# Ethernet.net
KiCad netlist of a schematic drawn in Altium Designer
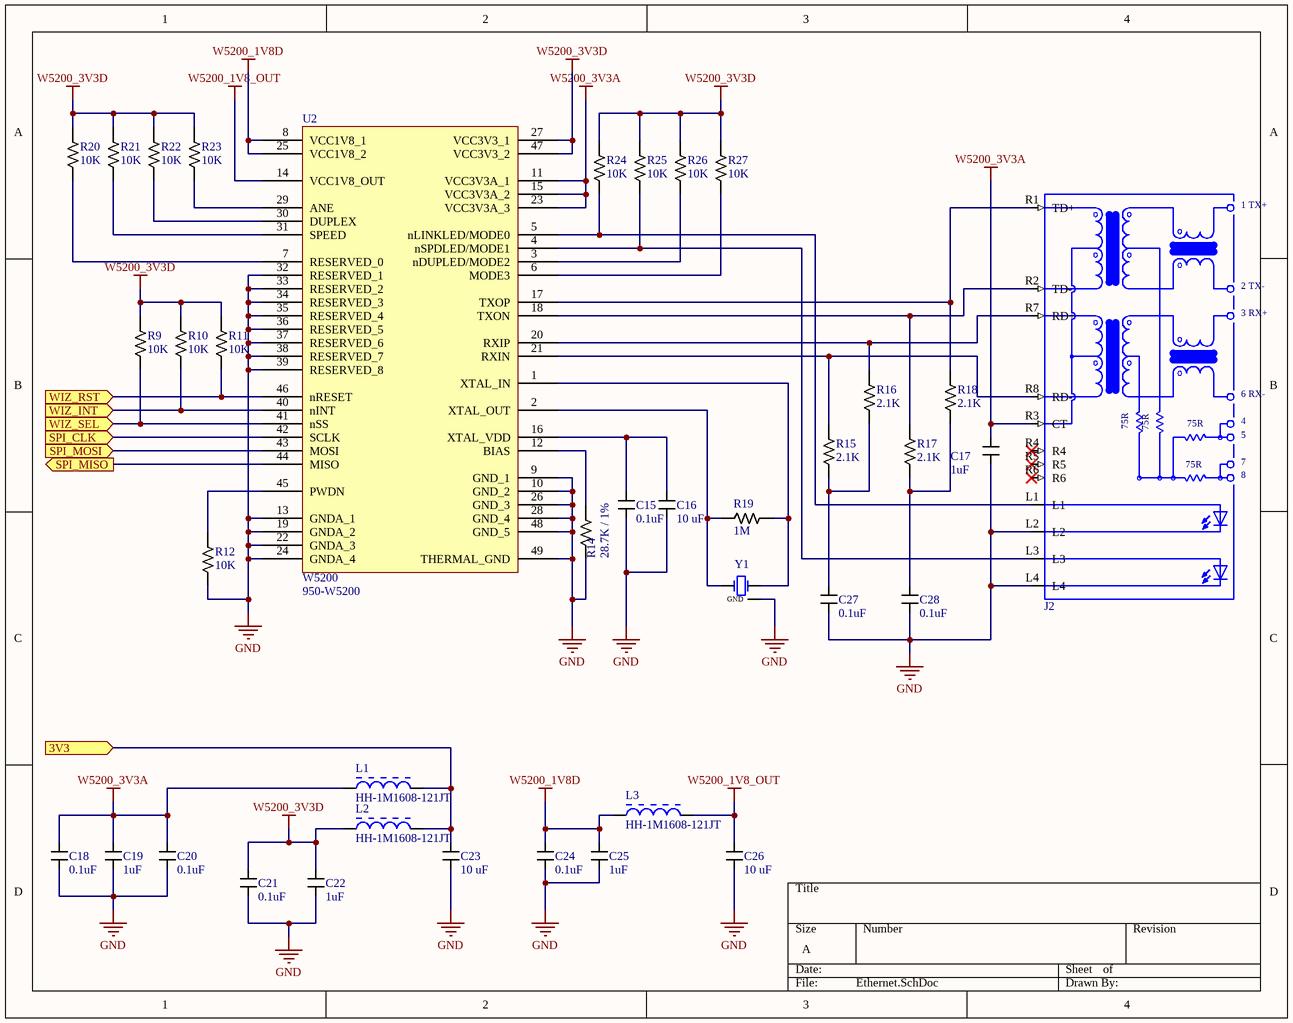
[diagram p0: Ethernet.SchDoc]

(export (version "E")
  (design (tool "Eeschema 10.0.6"))
  (components
    (comp (ref "C15")
      (value "0.1uF")
      (footprint "CAPACITOR_0603")
      (description "Cap 100nF 6.3V +/-10%\r\nCeramic 0603")
      (fields
        (field (name "TOLERANCE") "+/- 10%")
        (field (name "VOLTAGE") "6.3V")
        (field (name "MADE BY") "Flip B")
      )
      (libsource (lib "Capacitors") (part "CAPACITOR_0.1uF_0603"))
    )
    (comp (ref "C16")
      (value "10uF Ceramic 6.3V")
      (footprint "CAPACITOR_0603")
      (description "Cap 10uF 6.3V +/-20%\r\nCeramic 0603")
      (fields
        (field (name "TOLERANCE") "+/- 20%")
        (field (name "VOLTAGE") "6.3V")
        (field (name "VALUE (UF)") "10 uF")
        (field (name "MADE BY") "Flip B")
      )
      (libsource (lib "Capacitors") (part "CAPACITOR_10uF_0603"))
    )
    (comp (ref "C17")
      (value "1uF")
      (footprint "CAPACITOR_0603")
      (description "Cap 1uF 16V +/-10%\r\nCeramic 0603")
      (fields
        (field (name "TOLERANCE") "+/- 10%")
        (field (name "VOLTAGE") "16V")
        (field (name "MADE BY") "Flip B")
      )
      (libsource (lib "Capacitors") (part "CAPACITOR_1uF_0603"))
    )
    (comp (ref "C18")
      (value "0.1uF")
      (footprint "CAPACITOR_0603")
      (description "Cap 100nF 6.3V +/-10%\r\nCeramic 0603")
      (fields
        (field (name "TOLERANCE") "+/- 10%")
        (field (name "VOLTAGE") "6.3V")
        (field (name "MADE BY") "Flip B")
      )
      (libsource (lib "Capacitors") (part "CAPACITOR_0.1uF_0603"))
    )
    (comp (ref "C19")
      (value "1uF")
      (footprint "CAPACITOR_0603")
      (description "Cap 1uF 16V +/-10%\r\nCeramic 0603")
      (fields
        (field (name "TOLERANCE") "+/- 10%")
        (field (name "VOLTAGE") "16V")
        (field (name "MADE BY") "Flip B")
      )
      (libsource (lib "Capacitors") (part "CAPACITOR_1uF_0603"))
    )
    (comp (ref "C20")
      (value "0.1uF")
      (footprint "CAPACITOR_0603")
      (description "Cap 100nF 6.3V +/-10%\r\nCeramic 0603")
      (fields
        (field (name "TOLERANCE") "+/- 10%")
        (field (name "VOLTAGE") "6.3V")
        (field (name "MADE BY") "Flip B")
      )
      (libsource (lib "Capacitors") (part "CAPACITOR_0.1uF_0603"))
    )
    (comp (ref "C21")
      (value "0.1uF")
      (footprint "CAPACITOR_0603")
      (description "Cap 100nF 6.3V +/-10%\r\nCeramic 0603")
      (fields
        (field (name "TOLERANCE") "+/- 10%")
        (field (name "VOLTAGE") "6.3V")
        (field (name "MADE BY") "Flip B")
      )
      (libsource (lib "Capacitors") (part "CAPACITOR_0.1uF_0603"))
    )
    (comp (ref "C22")
      (value "1uF")
      (footprint "CAPACITOR_0603")
      (description "Cap 1uF 16V +/-10%\r\nCeramic 0603")
      (fields
        (field (name "TOLERANCE") "+/- 10%")
        (field (name "VOLTAGE") "16V")
        (field (name "MADE BY") "Flip B")
      )
      (libsource (lib "Capacitors") (part "CAPACITOR_1uF_0603"))
    )
    (comp (ref "C23")
      (value "10uF Ceramic 6.3V")
      (footprint "CAPACITOR_0603")
      (description "Cap 10uF 6.3V +/-20%\r\nCeramic 0603")
      (fields
        (field (name "TOLERANCE") "+/- 20%")
        (field (name "VOLTAGE") "6.3V")
        (field (name "VALUE (UF)") "10 uF")
        (field (name "MADE BY") "Flip B")
      )
      (libsource (lib "Capacitors") (part "CAPACITOR_10uF_0603"))
    )
    (comp (ref "C24")
      (value "0.1uF")
      (footprint "CAPACITOR_0603")
      (description "Cap 100nF 6.3V +/-10%\r\nCeramic 0603")
      (fields
        (field (name "TOLERANCE") "+/- 10%")
        (field (name "VOLTAGE") "6.3V")
        (field (name "MADE BY") "Flip B")
      )
      (libsource (lib "Capacitors") (part "CAPACITOR_0.1uF_0603"))
    )
    (comp (ref "C25")
      (value "1uF")
      (footprint "CAPACITOR_0603")
      (description "Cap 1uF 16V +/-10%\r\nCeramic 0603")
      (fields
        (field (name "TOLERANCE") "+/- 10%")
        (field (name "VOLTAGE") "16V")
        (field (name "MADE BY") "Flip B")
      )
      (libsource (lib "Capacitors") (part "CAPACITOR_1uF_0603"))
    )
    (comp (ref "C26")
      (value "10uF Ceramic 6.3V")
      (footprint "CAPACITOR_0603")
      (description "Cap 10uF 6.3V +/-20%\r\nCeramic 0603")
      (fields
        (field (name "TOLERANCE") "+/- 20%")
        (field (name "VOLTAGE") "6.3V")
        (field (name "VALUE (UF)") "10 uF")
        (field (name "MADE BY") "Flip B")
      )
      (libsource (lib "Capacitors") (part "CAPACITOR_10uF_0603"))
    )
    (comp (ref "C27")
      (value "0.1uF")
      (footprint "CAPACITOR_0603")
      (description "Cap 100nF 6.3V +/-10%\r\nCeramic 0603")
      (fields
        (field (name "TOLERANCE") "+/- 10%")
        (field (name "VOLTAGE") "6.3V")
        (field (name "MADE BY") "Flip B")
      )
      (libsource (lib "Capacitors") (part "CAPACITOR_0.1uF_0603"))
    )
    (comp (ref "C28")
      (value "0.1uF")
      (footprint "CAPACITOR_0603")
      (description "Cap 100nF 6.3V +/-10%\r\nCeramic 0603")
      (fields
        (field (name "TOLERANCE") "+/- 10%")
        (field (name "VOLTAGE") "6.3V")
        (field (name "MADE BY") "Flip B")
      )
      (libsource (lib "Capacitors") (part "CAPACITOR_0.1uF_0603"))
    )
    (comp (ref "J2")
      (value "Ethernet Connector")
      (footprint "WIZNET_RB1-125BAG1A")
      (description "CONN JACK 1PORT 100 BASE-T PCB")
      (libsource (lib "Connectors") (part "RB1-125BAG1A"))
    )
    (comp (ref "L1")
      (value "HH-1M1608-121JT")
      (footprint "CTC-1608_L")
      (description "Chip Ferrite Bead, 0.14 Ohm, 1.1 A, -55 to 125 degC, 2-Pin SMD, RoHS, Tape and Reel")
      (fields (field (name "MANUFACTURER") "CTC Coils") (field (name "PARTNUMBER") "HH-1M1608"))
      (libsource (lib "Altium Content Vault") (part "IND-FB-2"))
    )
    (comp (ref "L2")
      (value "HH-1M1608-121JT")
      (footprint "CTC-1608_L")
      (description "Chip Ferrite Bead, 0.14 Ohm, 1.1 A, -55 to 125 degC, 2-Pin SMD, RoHS, Tape and Reel")
      (fields (field (name "MANUFACTURER") "CTC Coils") (field (name "PARTNUMBER") "HH-1M1608"))
      (libsource (lib "Altium Content Vault") (part "IND-FB-2"))
    )
    (comp (ref "L3")
      (value "HH-1M1608-121JT")
      (footprint "CTC-1608_L")
      (description "Chip Ferrite Bead, 0.14 Ohm, 1.1 A, -55 to 125 degC, 2-Pin SMD, RoHS, Tape and Reel")
      (fields (field (name "MANUFACTURER") "CTC Coils") (field (name "PARTNUMBER") "HH-1M1608"))
      (libsource (lib "Altium Content Vault") (part "IND-FB-2"))
    )
    (comp (ref "R9")
      (value "10k Ohm 5% 1/10W")
      (footprint "RESISTOR_0603")
      (description "RES 10k OHM 5% 1/10W 0603")
      (fields
        (field (name "TOLERANCE") "+/- 5%")
        (field (name "VALUE  (OHMS)") "10K")
        (field (name "MADE BY") "Robert Pafford")
      )
      (libsource (lib "Resistors") (part "RESISTOR_10K_0603"))
    )
    (comp (ref "R10")
      (value "10k Ohm 5% 1/10W")
      (footprint "RESISTOR_0603")
      (description "RES 10k OHM 5% 1/10W 0603")
      (fields
        (field (name "TOLERANCE") "+/- 5%")
        (field (name "VALUE  (OHMS)") "10K")
        (field (name "MADE BY") "Robert Pafford")
      )
      (libsource (lib "Resistors") (part "RESISTOR_10K_0603"))
    )
    (comp (ref "R11")
      (value "10k Ohm 5% 1/10W")
      (footprint "RESISTOR_0603")
      (description "RES 10k OHM 5% 1/10W 0603")
      (fields
        (field (name "TOLERANCE") "+/- 5%")
        (field (name "VALUE  (OHMS)") "10K")
        (field (name "MADE BY") "Robert Pafford")
      )
      (libsource (lib "Resistors") (part "RESISTOR_10K_0603"))
    )
    (comp (ref "R12")
      (value "10k Ohm 5% 1/10W")
      (footprint "RESISTOR_0603")
      (description "RES 10k OHM 5% 1/10W 0603")
      (fields
        (field (name "TOLERANCE") "+/- 5%")
        (field (name "VALUE  (OHMS)") "10K")
        (field (name "MADE BY") "Robert Pafford")
      )
      (libsource (lib "Resistors") (part "RESISTOR_10K_0603"))
    )
    (comp (ref "R14")
      (value "K / 1%")
      (footprint "RESISTOR_0603")
      (description "RES 28.7K OHM 1% 1/8W 0603")
      (fields
        (field (name "TOLERANCE") "+/- 5%")
        (field (name "VALUE  (OHMS)") "28.7K / 1%")
        (field (name "MADE BY") "Robert Pafford")
      )
      (libsource (lib "Resistors") (part "RESISTOR_28.7K / 1%_0603_1"))
    )
    (comp (ref "R15")
      (value "2.1k Ohm 5% 1/8W")
      (footprint "RESISTOR_0603")
      (description "RES 2.1k OHM 5% 1/8W 0603")
      (fields
        (field (name "TOLERANCE") "+/- 5%")
        (field (name "VALUE  (OHMS)") "2.1K")
        (field (name "MADE BY") "Robert Pafford")
      )
      (libsource (lib "Resistors") (part "RESISTOR_2.1K_0603_1"))
    )
    (comp (ref "R16")
      (value "2.1k Ohm 5% 1/8W")
      (footprint "RESISTOR_0603")
      (description "RES 2.1k OHM 5% 1/8W 0603")
      (fields
        (field (name "TOLERANCE") "+/- 5%")
        (field (name "VALUE  (OHMS)") "2.1K")
        (field (name "MADE BY") "Robert Pafford")
      )
      (libsource (lib "Resistors") (part "RESISTOR_2.1K_0603_1"))
    )
    (comp (ref "R17")
      (value "2.1k Ohm 5% 1/8W")
      (footprint "RESISTOR_0603")
      (description "RES 2.1k OHM 5% 1/8W 0603")
      (fields
        (field (name "TOLERANCE") "+/- 5%")
        (field (name "VALUE  (OHMS)") "2.1K")
        (field (name "MADE BY") "Robert Pafford")
      )
      (libsource (lib "Resistors") (part "RESISTOR_2.1K_0603_1"))
    )
    (comp (ref "R18")
      (value "2.1k Ohm 5% 1/8W")
      (footprint "RESISTOR_0603")
      (description "RES 2.1k OHM 5% 1/8W 0603")
      (fields
        (field (name "TOLERANCE") "+/- 5%")
        (field (name "VALUE  (OHMS)") "2.1K")
        (field (name "MADE BY") "Robert Pafford")
      )
      (libsource (lib "Resistors") (part "RESISTOR_2.1K_0603_1"))
    )
    (comp (ref "R19")
      (value "1M")
      (footprint "RESISTOR_0603")
      (description "RES 1M OHM 1/8W 0603")
      (fields
        (field (name "TOLERANCE") "+/- 5%")
        (field (name "VALUE  (OHMS)") "1M")
        (field (name "MADE BY") "Robert Pafford")
      )
      (libsource (lib "Resistors") (part "RESISTOR_1M_0603_1"))
    )
    (comp (ref "R20")
      (value "10k Ohm 5% 1/10W")
      (footprint "RESISTOR_0603")
      (description "RES 10k OHM 5% 1/10W 0603")
      (fields
        (field (name "TOLERANCE") "+/- 5%")
        (field (name "VALUE  (OHMS)") "10K")
        (field (name "MADE BY") "Robert Pafford")
      )
      (libsource (lib "Resistors") (part "RESISTOR_10K_0603"))
    )
    (comp (ref "R21")
      (value "10k Ohm 5% 1/10W")
      (footprint "RESISTOR_0603")
      (description "RES 10k OHM 5% 1/10W 0603")
      (fields
        (field (name "TOLERANCE") "+/- 5%")
        (field (name "VALUE  (OHMS)") "10K")
        (field (name "MADE BY") "Robert Pafford")
      )
      (libsource (lib "Resistors") (part "RESISTOR_10K_0603"))
    )
    (comp (ref "R22")
      (value "10k Ohm 5% 1/10W")
      (footprint "RESISTOR_0603")
      (description "RES 10k OHM 5% 1/10W 0603")
      (fields
        (field (name "TOLERANCE") "+/- 5%")
        (field (name "VALUE  (OHMS)") "10K")
        (field (name "MADE BY") "Robert Pafford")
      )
      (libsource (lib "Resistors") (part "RESISTOR_10K_0603"))
    )
    (comp (ref "R23")
      (value "10k Ohm 5% 1/10W")
      (footprint "RESISTOR_0603")
      (description "RES 10k OHM 5% 1/10W 0603")
      (fields
        (field (name "TOLERANCE") "+/- 5%")
        (field (name "VALUE  (OHMS)") "10K")
        (field (name "MADE BY") "Robert Pafford")
      )
      (libsource (lib "Resistors") (part "RESISTOR_10K_0603"))
    )
    (comp (ref "R24")
      (value "10k Ohm 5% 1/10W")
      (footprint "RESISTOR_0603")
      (description "RES 10k OHM 5% 1/10W 0603")
      (fields
        (field (name "TOLERANCE") "+/- 5%")
        (field (name "VALUE  (OHMS)") "10K")
        (field (name "MADE BY") "Robert Pafford")
      )
      (libsource (lib "Resistors") (part "RESISTOR_10K_0603"))
    )
    (comp (ref "R25")
      (value "10k Ohm 5% 1/10W")
      (footprint "RESISTOR_0603")
      (description "RES 10k OHM 5% 1/10W 0603")
      (fields
        (field (name "TOLERANCE") "+/- 5%")
        (field (name "VALUE  (OHMS)") "10K")
        (field (name "MADE BY") "Robert Pafford")
      )
      (libsource (lib "Resistors") (part "RESISTOR_10K_0603"))
    )
    (comp (ref "R26")
      (value "10k Ohm 5% 1/10W")
      (footprint "RESISTOR_0603")
      (description "RES 10k OHM 5% 1/10W 0603")
      (fields
        (field (name "TOLERANCE") "+/- 5%")
        (field (name "VALUE  (OHMS)") "10K")
        (field (name "MADE BY") "Robert Pafford")
      )
      (libsource (lib "Resistors") (part "RESISTOR_10K_0603"))
    )
    (comp (ref "R27")
      (value "10k Ohm 5% 1/10W")
      (footprint "RESISTOR_0603")
      (description "RES 10k OHM 5% 1/10W 0603")
      (fields
        (field (name "TOLERANCE") "+/- 5%")
        (field (name "VALUE  (OHMS)") "10K")
        (field (name "MADE BY") "Robert Pafford")
      )
      (libsource (lib "Resistors") (part "RESISTOR_10K_0603"))
    )
    (comp (ref "U2")
      (value "W5200")
      (footprint "QFN-48")
      (description "WIZNET W5200\r\n48QFN (7x7 mm)")
      (fields
        (field (name "MF") "Texas Instruments")
        (field (name "MP") "LM1117IMPX-3.3/NOPB")
        (field (name "SUPPLIER PART NUMBER 1") "950-W5200")
        (field (name "CREATED BY:") "Siddharth.V")
      )
      (libsource (lib "Integrated Circuits") (part "W5200"))
    )
    (comp (ref "Y1")
      (value "CRYSTAL 12.0000MHZ 18PF SMD")
      (footprint "4-SMD No Lead Crystal")
      (description "25 MHz ±20ppm Crystal 18pF")
      (fields (field (name "MADE BY") "Robert Pafford"))
      (libsource (lib "Crystals") (part "CRYSTAL_25MHz_SMD_1"))
    )
  )
  (nets
    (net (code "1") (name "/3V3") (class "Default")
      (node (ref "C23") (pin "1") (pinfunction "1_1") (pintype "passive"))
      (node (ref "L1") (pin "2") (pinfunction "2_2") (pintype "passive"))
      (node (ref "L2") (pin "2") (pinfunction "2_2") (pintype "passive"))
    )
    (net (code "2") (name "/SPI_CLK") (class "Default")
      (node (ref "U2") (pin "42") (pinfunction "SCLK_42") (pintype "passive"))
    )
    (net (code "3") (name "/SPI_MISO") (class "Default")
      (node (ref "U2") (pin "44") (pinfunction "MISO_44") (pintype "passive"))
    )
    (net (code "4") (name "/SPI_MOSI") (class "Default")
      (node (ref "U2") (pin "43") (pinfunction "MOSI_43") (pintype "passive"))
    )
    (net (code "5") (name "/WIZ_INT") (class "Default")
      (node (ref "R10") (pin "2") (pinfunction "2_2") (pintype "passive"))
      (node (ref "U2") (pin "40") (pinfunction "nINT_40") (pintype "passive"))
    )
    (net (code "6") (name "/WIZ_RST") (class "Default")
      (node (ref "R11") (pin "2") (pinfunction "2_2") (pintype "passive"))
      (node (ref "U2") (pin "46") (pinfunction "nRESET_46") (pintype "passive"))
    )
    (net (code "7") (name "/WIZ_SEL") (class "Default")
      (node (ref "R9") (pin "2") (pinfunction "2_2") (pintype "passive"))
      (node (ref "U2") (pin "41") (pinfunction "nSS_41") (pintype "passive"))
    )
    (net (code "8") (name "GND") (class "Default")
      (node (ref "C15") (pin "2") (pinfunction "2_2") (pintype "passive"))
      (node (ref "C16") (pin "2") (pinfunction "2_2") (pintype "passive"))
      (node (ref "C17") (pin "2") (pinfunction "2_2") (pintype "passive"))
      (node (ref "C18") (pin "2") (pinfunction "2_2") (pintype "passive"))
      (node (ref "C19") (pin "2") (pinfunction "2_2") (pintype "passive"))
      (node (ref "C20") (pin "2") (pinfunction "2_2") (pintype "passive"))
      (node (ref "C21") (pin "2") (pinfunction "2_2") (pintype "passive"))
      (node (ref "C22") (pin "2") (pinfunction "2_2") (pintype "passive"))
      (node (ref "C23") (pin "2") (pinfunction "2_2") (pintype "passive"))
      (node (ref "C24") (pin "2") (pinfunction "2_2") (pintype "passive"))
      (node (ref "C25") (pin "2") (pinfunction "2_2") (pintype "passive"))
      (node (ref "C26") (pin "2") (pinfunction "2_2") (pintype "passive"))
      (node (ref "C27") (pin "2") (pinfunction "2_2") (pintype "passive"))
      (node (ref "C28") (pin "2") (pinfunction "2_2") (pintype "passive"))
      (node (ref "J2") (pin "L2") (pinfunction "L2_L2") (pintype "passive"))
      (node (ref "J2") (pin "L4") (pinfunction "L4_L4") (pintype "passive"))
      (node (ref "R12") (pin "2") (pinfunction "2_2") (pintype "passive"))
      (node (ref "R14") (pin "2") (pinfunction "2_2") (pintype "passive"))
      (node (ref "U2") (pin "10") (pinfunction "GND_2_10") (pintype "passive"))
      (node (ref "U2") (pin "13") (pinfunction "GNDA_1_13") (pintype "passive"))
      (node (ref "U2") (pin "19") (pinfunction "GNDA_2_19") (pintype "passive"))
      (node (ref "U2") (pin "22") (pinfunction "GNDA_3_22") (pintype "passive"))
      (node (ref "U2") (pin "24") (pinfunction "GNDA_4_24") (pintype "passive"))
      (node (ref "U2") (pin "26") (pinfunction "GND_3_26") (pintype "passive"))
      (node (ref "U2") (pin "28") (pinfunction "GND_4_28") (pintype "passive"))
      (node (ref "U2") (pin "32") (pinfunction "RESERVED_1_32") (pintype "passive"))
      (node (ref "U2") (pin "33") (pinfunction "RESERVED_2_33") (pintype "passive"))
      (node (ref "U2") (pin "34") (pinfunction "RESERVED_3_34") (pintype "passive"))
      (node (ref "U2") (pin "35") (pinfunction "RESERVED_4_35") (pintype "passive"))
      (node (ref "U2") (pin "36") (pinfunction "RESERVED_5_36") (pintype "passive"))
      (node (ref "U2") (pin "37") (pinfunction "RESERVED_6_37") (pintype "passive"))
      (node (ref "U2") (pin "38") (pinfunction "RESERVED_7_38") (pintype "passive"))
      (node (ref "U2") (pin "39") (pinfunction "RESERVED_8_39") (pintype "passive"))
      (node (ref "U2") (pin "48") (pinfunction "GND_5_48") (pintype "passive"))
      (node (ref "U2") (pin "49") (pinfunction "THERMAL_GND_49") (pintype "passive"))
      (node (ref "U2") (pin "9") (pinfunction "GND_1_9") (pintype "passive"))
      (node (ref "Y1") (pin "GND") (pinfunction "GND_GND") (pintype "power_in"))
    )
    (net (code "9") (name "Net-(C27-Pad1)") (class "Default")
      (node (ref "C27") (pin "1") (pinfunction "1_1") (pintype "passive"))
      (node (ref "R15") (pin "2") (pinfunction "2_2") (pintype "passive"))
      (node (ref "R16") (pin "2") (pinfunction "2_2") (pintype "passive"))
    )
    (net (code "10") (name "Net-(C28-Pad1)") (class "Default")
      (node (ref "C28") (pin "1") (pinfunction "1_1") (pintype "passive"))
      (node (ref "R17") (pin "2") (pinfunction "2_2") (pintype "passive"))
      (node (ref "R18") (pin "2") (pinfunction "2_2") (pintype "passive"))
    )
    (net (code "11") (name "Net-(J2-RD+)") (class "Default")
      (node (ref "J2") (pin "R7") (pinfunction "RD+_R7") (pintype "input"))
      (node (ref "R16") (pin "1") (pinfunction "1_1") (pintype "passive"))
      (node (ref "U2") (pin "20") (pinfunction "RXIP_20") (pintype "passive"))
    )
    (net (code "12") (name "Net-(J2-RD-)") (class "Default")
      (node (ref "J2") (pin "R8") (pinfunction "RD-_R8") (pintype "input"))
      (node (ref "R15") (pin "1") (pinfunction "1_1") (pintype "passive"))
      (node (ref "U2") (pin "21") (pinfunction "RXIN_21") (pintype "passive"))
    )
    (net (code "13") (name "Net-(J2-TD+)") (class "Default")
      (node (ref "J2") (pin "R1") (pinfunction "TD+_R1") (pintype "input"))
      (node (ref "R18") (pin "1") (pinfunction "1_1") (pintype "passive"))
      (node (ref "U2") (pin "17") (pinfunction "TXOP_17") (pintype "passive"))
    )
    (net (code "14") (name "Net-(J2-TD-)") (class "Default")
      (node (ref "J2") (pin "R2") (pinfunction "TD-_R2") (pintype "input"))
      (node (ref "R17") (pin "1") (pinfunction "1_1") (pintype "passive"))
      (node (ref "U2") (pin "18") (pinfunction "TXON_18") (pintype "passive"))
    )
    (net (code "15") (name "Net-(U2-ANE)") (class "Default")
      (node (ref "R23") (pin "2") (pinfunction "2_2") (pintype "passive"))
      (node (ref "U2") (pin "29") (pinfunction "ANE_29") (pintype "passive"))
    )
    (net (code "16") (name "Net-(U2-BIAS)") (class "Default")
      (node (ref "R14") (pin "1") (pinfunction "1_1") (pintype "passive"))
      (node (ref "U2") (pin "12") (pinfunction "BIAS_12") (pintype "passive"))
    )
    (net (code "17") (name "Net-(U2-DUPLEX)") (class "Default")
      (node (ref "R22") (pin "2") (pinfunction "2_2") (pintype "passive"))
      (node (ref "U2") (pin "30") (pinfunction "DUPLEX_30") (pintype "passive"))
    )
    (net (code "18") (name "Net-(U2-MODE3)") (class "Default")
      (node (ref "R27") (pin "2") (pinfunction "2_2") (pintype "passive"))
      (node (ref "U2") (pin "6") (pinfunction "MODE3_6") (pintype "passive"))
    )
    (net (code "19") (name "Net-(U2-PWDN)") (class "Default")
      (node (ref "R12") (pin "1") (pinfunction "1_1") (pintype "passive"))
      (node (ref "U2") (pin "45") (pinfunction "PWDN_45") (pintype "passive"))
    )
    (net (code "20") (name "Net-(U2-RESERVED_0)") (class "Default")
      (node (ref "R20") (pin "2") (pinfunction "2_2") (pintype "passive"))
      (node (ref "U2") (pin "7") (pinfunction "RESERVED_0_7") (pintype "passive"))
    )
    (net (code "21") (name "Net-(U2-SPEED)") (class "Default")
      (node (ref "R21") (pin "2") (pinfunction "2_2") (pintype "passive"))
      (node (ref "U2") (pin "31") (pinfunction "SPEED_31") (pintype "passive"))
    )
    (net (code "22") (name "Net-(U2-XTAL_IN)") (class "Default")
      (node (ref "R19") (pin "1") (pinfunction "1_1") (pintype "passive"))
      (node (ref "U2") (pin "1") (pinfunction "XTAL_IN_1") (pintype "passive"))
      (node (ref "Y1") (pin "2") (pinfunction "2_2") (pintype "passive"))
    )
    (net (code "23") (name "Net-(U2-XTAL_OUT)") (class "Default")
      (node (ref "R19") (pin "2") (pinfunction "2_2") (pintype "passive"))
      (node (ref "U2") (pin "2") (pinfunction "XTAL_OUT_2") (pintype "passive"))
      (node (ref "Y1") (pin "1") (pinfunction "1_1") (pintype "passive"))
    )
    (net (code "24") (name "Net-(U2-XTAL_VDD)") (class "Default")
      (node (ref "C15") (pin "1") (pinfunction "1_1") (pintype "passive"))
      (node (ref "C16") (pin "1") (pinfunction "1_1") (pintype "passive"))
      (node (ref "U2") (pin "16") (pinfunction "XTAL_VDD_16") (pintype "passive"))
    )
    (net (code "25") (name "Net-(U2-nDUPLED{slash}MODE2)") (class "Default")
      (node (ref "R26") (pin "2") (pinfunction "2_2") (pintype "passive"))
      (node (ref "U2") (pin "3") (pinfunction "nDUPLED/MODE2_3") (pintype "passive"))
    )
    (net (code "26") (name "Net-(U2-nLINKLED{slash}MODE0)") (class "Default")
      (node (ref "J2") (pin "L1") (pinfunction "L1_L1") (pintype "passive"))
      (node (ref "R24") (pin "2") (pinfunction "2_2") (pintype "passive"))
      (node (ref "U2") (pin "5") (pinfunction "nLINKLED/MODE0_5") (pintype "passive"))
    )
    (net (code "27") (name "Net-(U2-nSPDLED{slash}MODE1)") (class "Default")
      (node (ref "J2") (pin "L3") (pinfunction "L3_L3") (pintype "passive"))
      (node (ref "R25") (pin "2") (pinfunction "2_2") (pintype "passive"))
      (node (ref "U2") (pin "4") (pinfunction "nSPDLED/MODE1_4") (pintype "passive"))
    )
    (net (code "28") (name "W5200_1V8D") (class "Default")
      (node (ref "C24") (pin "1") (pinfunction "1_1") (pintype "passive"))
      (node (ref "C25") (pin "1") (pinfunction "1_1") (pintype "passive"))
      (node (ref "L3") (pin "1") (pinfunction "1_1") (pintype "passive"))
      (node (ref "U2") (pin "25") (pinfunction "VCC1V8_2_25") (pintype "passive"))
      (node (ref "U2") (pin "8") (pinfunction "VCC1V8_1_8") (pintype "passive"))
    )
    (net (code "29") (name "W5200_1V8_OUT") (class "Default")
      (node (ref "C26") (pin "1") (pinfunction "1_1") (pintype "passive"))
      (node (ref "L3") (pin "2") (pinfunction "2_2") (pintype "passive"))
      (node (ref "U2") (pin "14") (pinfunction "VCC1V8_OUT_14") (pintype "passive"))
    )
    (net (code "30") (name "W5200_3V3A") (class "Default")
      (node (ref "C17") (pin "1") (pinfunction "1_1") (pintype "passive"))
      (node (ref "C18") (pin "1") (pinfunction "1_1") (pintype "passive"))
      (node (ref "C19") (pin "1") (pinfunction "1_1") (pintype "passive"))
      (node (ref "C20") (pin "1") (pinfunction "1_1") (pintype "passive"))
      (node (ref "J2") (pin "R3") (pinfunction "CT_R3") (pintype "input"))
      (node (ref "L1") (pin "1") (pinfunction "1_1") (pintype "passive"))
      (node (ref "U2") (pin "11") (pinfunction "VCC3V3A_1_11") (pintype "passive"))
      (node (ref "U2") (pin "15") (pinfunction "VCC3V3A_2_15") (pintype "passive"))
      (node (ref "U2") (pin "23") (pinfunction "VCC3V3A_3_23") (pintype "passive"))
    )
    (net (code "31") (name "W5200_3V3D") (class "Default")
      (node (ref "C21") (pin "1") (pinfunction "1_1") (pintype "passive"))
      (node (ref "C22") (pin "1") (pinfunction "1_1") (pintype "passive"))
      (node (ref "L2") (pin "1") (pinfunction "1_1") (pintype "passive"))
      (node (ref "R10") (pin "1") (pinfunction "1_1") (pintype "passive"))
      (node (ref "R11") (pin "1") (pinfunction "1_1") (pintype "passive"))
      (node (ref "R20") (pin "1") (pinfunction "1_1") (pintype "passive"))
      (node (ref "R21") (pin "1") (pinfunction "1_1") (pintype "passive"))
      (node (ref "R22") (pin "1") (pinfunction "1_1") (pintype "passive"))
      (node (ref "R23") (pin "1") (pinfunction "1_1") (pintype "passive"))
      (node (ref "R24") (pin "1") (pinfunction "1_1") (pintype "passive"))
      (node (ref "R25") (pin "1") (pinfunction "1_1") (pintype "passive"))
      (node (ref "R26") (pin "1") (pinfunction "1_1") (pintype "passive"))
      (node (ref "R27") (pin "1") (pinfunction "1_1") (pintype "passive"))
      (node (ref "R9") (pin "1") (pinfunction "1_1") (pintype "passive"))
      (node (ref "U2") (pin "27") (pinfunction "VCC3V3_1_27") (pintype "passive"))
      (node (ref "U2") (pin "47") (pinfunction "VCC3V3_2_47") (pintype "passive"))
    )
    (net (code "32") (name "unconnected-(J2-PadR4)") (class "Default")
      (node (ref "J2") (pin "R4") (pinfunction "R4_R4") (pintype "input+no_connect"))
    )
    (net (code "33") (name "unconnected-(J2-PadR5)") (class "Default")
      (node (ref "J2") (pin "R5") (pinfunction "R5_R5") (pintype "input+no_connect"))
    )
    (net (code "34") (name "unconnected-(J2-PadR6)") (class "Default")
      (node (ref "J2") (pin "R6") (pinfunction "R6_R6") (pintype "input+no_connect"))
    )
  )
)
